# Coil_Driver.net
KiCad netlist of a schematic drawn in Altium Designer
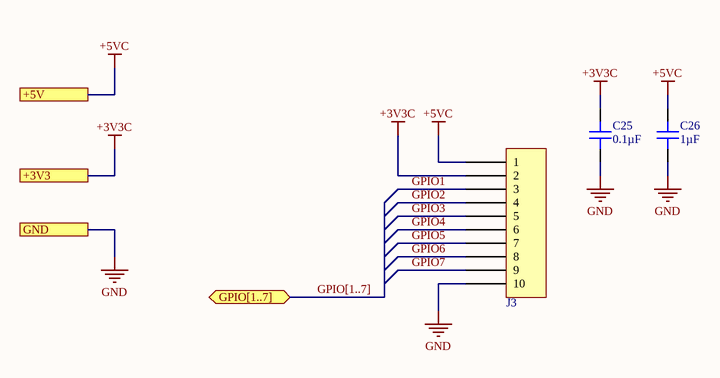
[diagram p0: Coil Driver.SchDoc]

(export (version "E")
  (design (tool "Eeschema 10.0.6"))
  (components
    (comp (ref "C25")
      (value "0.1µF")
      (footprint "CAP 0402_1005")
      (description "CAP CER 0.1UF 25V X7R 0402")
      (fields (field (name "PART NUMBER") "04023C104JAT2A") (field (name "MANUFACTURER") "AVX Corporation"))
      (libsource (lib "Generic Altium Database") (part "Capacitor"))
    )
    (comp (ref "C26")
      (value "1µF")
      (footprint "CAP 0402_1005")
      (description "CAP CER 1UF 16V X5R 0402")
      (fields (field (name "PART NUMBER") "0402BW105K160NGT") (field (name "MANUFACTURER") "Knowles Novacap"))
      (libsource (lib "Generic Altium Database") (part "Capacitor"))
    )
    (comp (ref "J3")
      (value "0022272101")
      (footprint "MOLEX KK 0022272101")
      (description "CONN HEADER VERT 10POS 2.54MM")
      (fields (field (name "MANUFACTURER") "Molex"))
      (libsource (lib "Generic Altium Database") (part "10 Pin"))
    )
  )
  (nets
    (net (code "1") (name "+3V3C") (class "Default")
      (node (ref "C25") (pin "2") (pinfunction "2_2") (pintype "passive"))
      (node (ref "J3") (pin "2") (pinfunction "2_2") (pintype "passive"))
    )
    (net (code "2") (name "+5VC") (class "Default")
      (node (ref "C26") (pin "2") (pinfunction "2_2") (pintype "passive"))
      (node (ref "J3") (pin "1") (pinfunction "1_1") (pintype "passive"))
    )
    (net (code "3") (name "/GPIO1") (class "Default")
      (node (ref "J3") (pin "3") (pinfunction "3_3") (pintype "passive"))
    )
    (net (code "4") (name "/GPIO2") (class "Default")
      (node (ref "J3") (pin "4") (pinfunction "4_4") (pintype "passive"))
    )
    (net (code "5") (name "/GPIO3") (class "Default")
      (node (ref "J3") (pin "5") (pinfunction "5_5") (pintype "passive"))
    )
    (net (code "6") (name "/GPIO4") (class "Default")
      (node (ref "J3") (pin "6") (pinfunction "6_6") (pintype "passive"))
    )
    (net (code "7") (name "/GPIO5") (class "Default")
      (node (ref "J3") (pin "7") (pinfunction "7_7") (pintype "passive"))
    )
    (net (code "8") (name "/GPIO6") (class "Default")
      (node (ref "J3") (pin "8") (pinfunction "8_8") (pintype "passive"))
    )
    (net (code "9") (name "/GPIO7") (class "Default")
      (node (ref "J3") (pin "9") (pinfunction "9_9") (pintype "passive"))
    )
    (net (code "11") (name "GND") (class "Default")
      (node (ref "C25") (pin "1") (pinfunction "1_1") (pintype "passive"))
      (node (ref "C26") (pin "1") (pinfunction "1_1") (pintype "passive"))
      (node (ref "J3") (pin "10") (pinfunction "10_10") (pintype "passive"))
    )
  )
)
